# design.net
KiCad netlist of a schematic drawn in Altium Designer
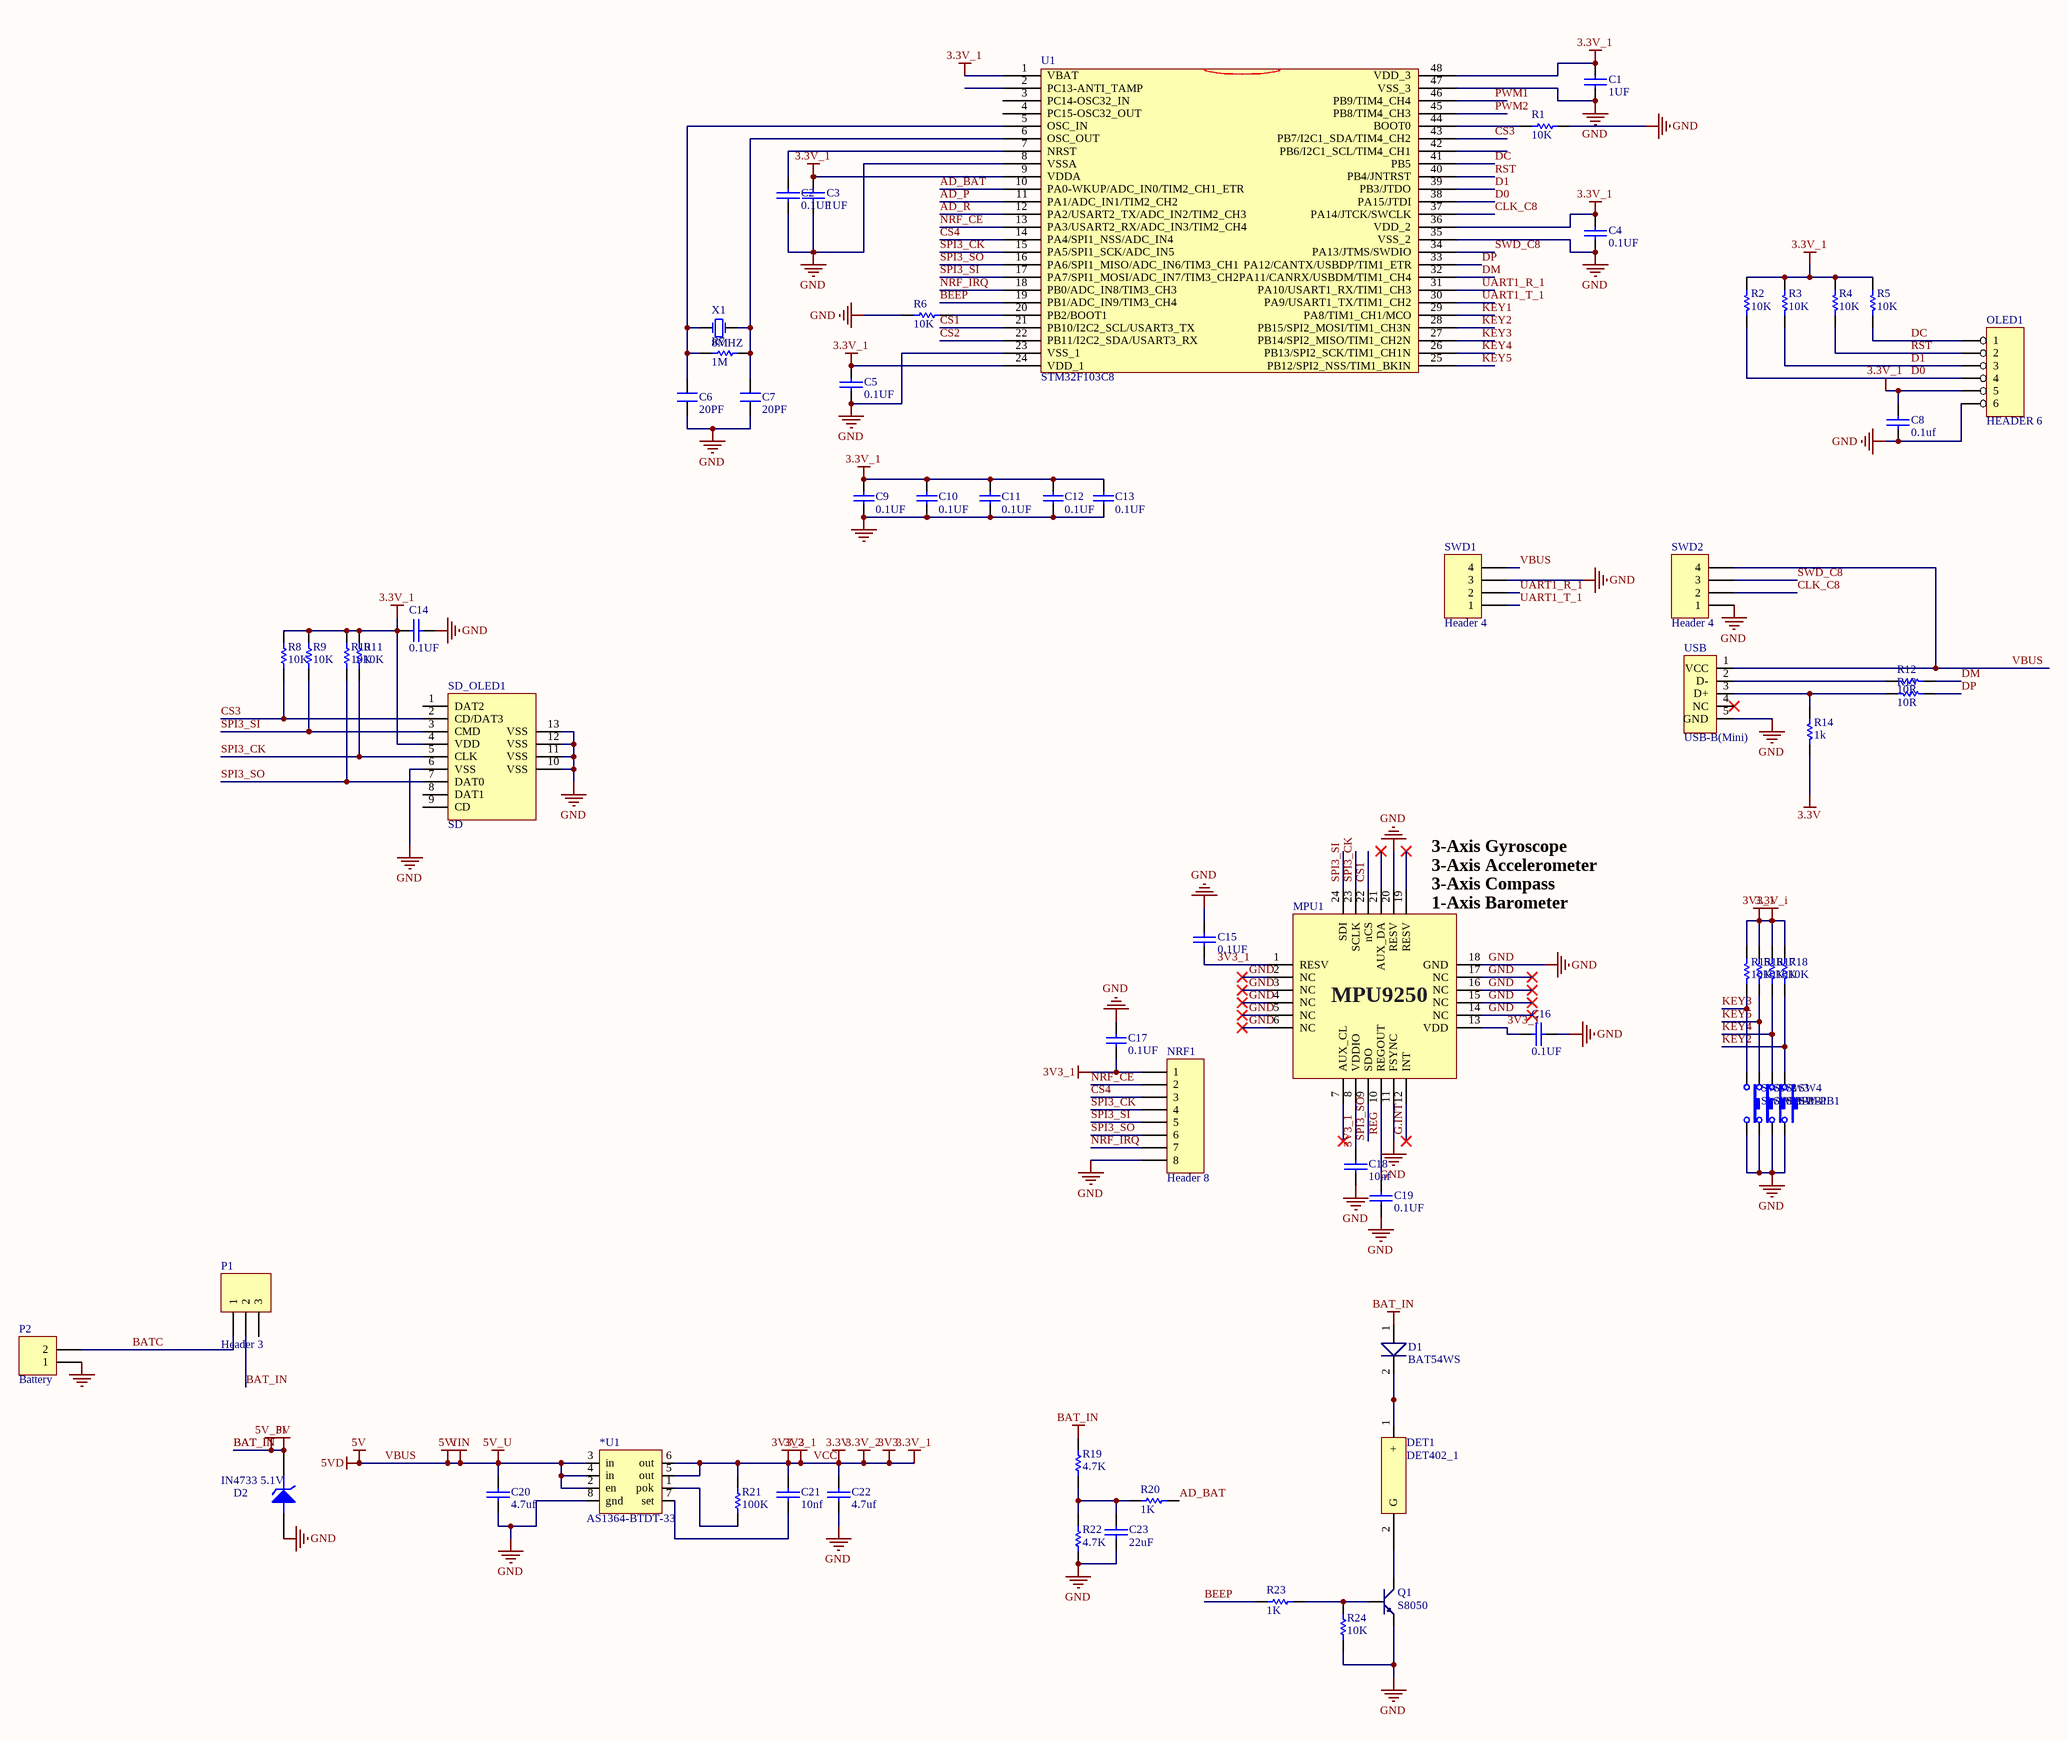
[diagram p0: 遥控器.SchDoc]

(export (version "E")
  (design (tool "Eeschema 10.0.6"))
  (components
    (comp (ref "*U1")
      (value "AS1364-BTDT-33")
      (footprint "TDFN-8")
      (libsource (lib "Schlib1_hand") (part "AS1364-3.3V"))
    )
    (comp (ref "C1")
      (value "1UF")
      (footprint "C 0402")
      (description "Capacitor")
      (libsource (lib "*") (part "CAP"))
    )
    (comp (ref "C2")
      (value "0.1UF")
      (footprint "C 0402")
      (description "Capacitor")
      (libsource (lib "*") (part "CAP"))
    )
    (comp (ref "C3")
      (value "1UF")
      (footprint "C 0402")
      (description "Capacitor")
      (libsource (lib "*") (part "CAP"))
    )
    (comp (ref "C4")
      (value "0.1UF")
      (footprint "C 0402")
      (description "Capacitor")
      (libsource (lib "*") (part "CAP"))
    )
    (comp (ref "C5")
      (value "0.1UF")
      (footprint "C 0402")
      (description "Capacitor")
      (libsource (lib "*") (part "CAP"))
    )
    (comp (ref "C6")
      (value "20PF")
      (footprint "C 0402")
      (description "0805")
      (libsource (lib "stm32f429i") (part "C2"))
    )
    (comp (ref "C7")
      (value "20PF")
      (footprint "C 0402")
      (description "0805")
      (libsource (lib "stm32f429i") (part "C2"))
    )
    (comp (ref "C8")
      (value "0.1uf")
      (footprint "C 0402")
      (description "Capacitor")
      (libsource (lib "*") (part "CAP"))
    )
    (comp (ref "C9")
      (value "0.1UF")
      (footprint "C 0402")
      (description "Capacitor")
      (fields (field (name "PUBLISHER") "Altium Limited"))
      (libsource (lib "Miscellaneous Devices") (part "CAP"))
    )
    (comp (ref "C10")
      (value "0.1UF")
      (footprint "C 0402")
      (description "Capacitor")
      (fields (field (name "PUBLISHER") "Altium Limited"))
      (libsource (lib "Miscellaneous Devices") (part "CAP"))
    )
    (comp (ref "C11")
      (value "0.1UF")
      (footprint "C 0402")
      (description "Capacitor")
      (fields (field (name "PUBLISHER") "Altium Limited"))
      (libsource (lib "Miscellaneous Devices") (part "CAP"))
    )
    (comp (ref "C12")
      (value "0.1UF")
      (footprint "C 0402")
      (description "Capacitor")
      (fields (field (name "PUBLISHER") "Altium Limited"))
      (libsource (lib "Miscellaneous Devices") (part "CAP"))
    )
    (comp (ref "C13")
      (value "0.1UF")
      (footprint "C 0402")
      (description "Capacitor")
      (fields (field (name "PUBLISHER") "Altium Limited"))
      (libsource (lib "Miscellaneous Devices") (part "CAP"))
    )
    (comp (ref "C14")
      (value "0.1UF")
      (footprint "C 0402")
      (description "Capacitor")
      (libsource (lib "*") (part "CAP"))
    )
    (comp (ref "C15")
      (value "0.1UF")
      (footprint "C 0402")
      (description "Capacitor")
      (libsource (lib "*") (part "CAP"))
    )
    (comp (ref "C16")
      (value "0.1UF")
      (footprint "C 0402")
      (description "Capacitor")
      (libsource (lib "*") (part "CAP"))
    )
    (comp (ref "C17")
      (value "0.1UF")
      (footprint "C 0402")
      (description "Capacitor")
      (fields (field (name "PUBLISHER") "Altium Limited"))
      (libsource (lib "Miscellaneous Devices") (part "CAP"))
    )
    (comp (ref "C18")
      (value "10nf")
      (footprint "C 0402")
      (description "Capacitor")
      (libsource (lib "*") (part "CAP"))
    )
    (comp (ref "C19")
      (value "0.1UF")
      (footprint "C 0402")
      (description "Capacitor")
      (libsource (lib "*") (part "CAP"))
    )
    (comp (ref "C20")
      (value "4.7uf")
      (footprint "C 0402")
      (description "Capacitor")
      (libsource (lib "*") (part "CAP"))
    )
    (comp (ref "C21")
      (value "10nf")
      (footprint "C 0402")
      (description "Capacitor")
      (libsource (lib "*") (part "CAP"))
    )
    (comp (ref "C22")
      (value "4.7uf")
      (footprint "C 0402")
      (description "Capacitor")
      (libsource (lib "*") (part "CAP"))
    )
    (comp (ref "C23")
      (value "22uF")
      (footprint "C 0402")
      (description "Capacitor")
      (libsource (lib "*") (part "CAP"))
    )
    (comp (ref "D1")
      (value "BAT54WS")
      (footprint "SOD-323")
      (description "单肖特基二极管")
      (libsource (lib "MiniFly ") (part "BAT54"))
    )
    (comp (ref "D2")
      (value "IN4733 5.1V")
      (footprint "1n4148-SOD123")
      (description "Zener Diode")
      (libsource (lib "*") (part "ZENER3"))
    )
    (comp (ref "DET1") (value "DET402_1") (footprint "DET402") (libsource (lib "EXPLORER") (part "DET402_1")))
    (comp (ref "MPU1")
      (value "MPU9250")
      (footprint "EXPLORER:MPU_QFN24_0.4")
      (description "Sensor")
      (libsource (lib "SCH_IC") (part "MPU9250"))
    )
    (comp (ref "NRF1")
      (value "Header 8")
      (footprint "NRF")
      (description "Header, 8-Pin")
      (fields (field (name "PUBLISHER") "Altium Limited"))
      (libsource (lib "Miscellaneous Connectors") (part "Header 8"))
    )
    (comp (ref "OLED1")
      (value "HEADER 6")
      (footprint "HDR1X6")
      (libsource (lib "Miscellaneous Devices") (part "HEADER 6"))
    )
    (comp (ref "P1")
      (value "Header 3")
      (footprint "HDR1X3")
      (description "Header, 3-Pin")
      (fields (field (name "PUBLISHER") "Altium Limited"))
      (libsource (lib "Miscellaneous Connectors") (part "Header 3"))
    )
    (comp (ref "P2")
      (value "Battery")
      (footprint "HDR1X2")
      (description "Header, 2-Pin")
      (fields (field (name "PUBLISHER") "Altium Limited"))
      (libsource (lib "MiniFly ") (part "Header 2"))
    )
    (comp (ref "Q1")
      (value "S8050")
      (footprint "SOT-23R")
      (description "8050/BCW846/BCW847")
      (libsource (lib "EXPLORER") (part "NPN"))
    )
    (comp (ref "R1")
      (value "10K")
      (footprint "R 0402")
      (description "Resistor")
      (fields (field (name "Comment") "1K") (field (name "PUBLISHER") "Altium Limited"))
      (libsource (lib "Miscellaneous Devices") (part "Res1"))
    )
    (comp (ref "R2")
      (value "10K")
      (footprint "R 0402")
      (description "0603")
      (libsource (lib "") (part "Res2_1"))
    )
    (comp (ref "R3")
      (value "10K")
      (footprint "R 0402")
      (description "0603")
      (libsource (lib "") (part "Res2_1"))
    )
    (comp (ref "R4")
      (value "10K")
      (footprint "R 0402")
      (description "0603")
      (libsource (lib "") (part "Res2_1"))
    )
    (comp (ref "R5")
      (value "10K")
      (footprint "R 0402")
      (description "0603")
      (libsource (lib "") (part "Res2_1"))
    )
    (comp (ref "R6")
      (value "10K")
      (footprint "R 0402")
      (description "Resistor")
      (fields (field (name "Comment") "1K") (field (name "PUBLISHER") "Altium Limited"))
      (libsource (lib "Miscellaneous Devices") (part "Res1"))
    )
    (comp (ref "R7")
      (value "1M")
      (footprint "R 0402")
      (description "0603")
      (libsource (lib "stm32f429i") (part "Res2"))
    )
    (comp (ref "R8")
      (value "10K")
      (footprint "R 0402")
      (description "0603")
      (libsource (lib "stm32f429i") (part "Res2"))
    )
    (comp (ref "R9")
      (value "10K")
      (footprint "R 0402")
      (description "0603")
      (libsource (lib "stm32f429i") (part "Res2"))
    )
    (comp (ref "R10")
      (value "10K")
      (footprint "R 0402")
      (description "0603")
      (libsource (lib "stm32f429i") (part "Res2"))
    )
    (comp (ref "R11")
      (value "10K")
      (footprint "R 0402")
      (description "0603")
      (libsource (lib "stm32f429i") (part "Res2"))
    )
    (comp (ref "R12")
      (value "10R")
      (footprint "R 0402")
      (description "0603")
      (libsource (lib "stm32f429i") (part "Res2"))
    )
    (comp (ref "R13")
      (value "10R")
      (footprint "R 0402")
      (description "0603")
      (libsource (lib "stm32f429i") (part "Res2"))
    )
    (comp (ref "R14")
      (value "1k")
      (footprint "R 0402")
      (description "0603")
      (libsource (lib "") (part "Res2_1"))
    )
    (comp (ref "R15")
      (value "10K")
      (footprint "R 0402")
      (description "Resistor")
      (fields (field (name "PUBLISHER") "Altium Limited"))
      (libsource (lib "Miscellaneous Devices") (part "Res1"))
    )
    (comp (ref "R16")
      (value "10K")
      (footprint "R 0402")
      (description "Resistor")
      (fields (field (name "PUBLISHER") "Altium Limited"))
      (libsource (lib "Miscellaneous Devices") (part "Res1"))
    )
    (comp (ref "R17")
      (value "10K")
      (footprint "R 0402")
      (description "Resistor")
      (fields (field (name "PUBLISHER") "Altium Limited"))
      (libsource (lib "Miscellaneous Devices") (part "Res1"))
    )
    (comp (ref "R18")
      (value "10K")
      (footprint "R 0402")
      (description "Resistor")
      (fields (field (name "PUBLISHER") "Altium Limited"))
      (libsource (lib "Miscellaneous Devices") (part "Res1"))
    )
    (comp (ref "R19")
      (value "4.7K")
      (footprint "R 0402")
      (description "0603")
      (libsource (lib "stm32f429i") (part "Res2"))
    )
    (comp (ref "R20")
      (value "1K")
      (footprint "R 0402")
      (description "0603")
      (libsource (lib "stm32f429i") (part "Res2"))
    )
    (comp (ref "R21")
      (value "100K")
      (footprint "R 0402")
      (description "Resistor")
      (fields (field (name "Comment") "1K") (field (name "PUBLISHER") "Altium Limited"))
      (libsource (lib "Miscellaneous Devices") (part "Res1"))
    )
    (comp (ref "R22")
      (value "4.7K")
      (footprint "R 0402")
      (description "0603")
      (libsource (lib "stm32f429i") (part "Res2"))
    )
    (comp (ref "R23")
      (value "1K")
      (footprint "R 0402")
      (description "0603")
      (libsource (lib "stm32f429i") (part "Res2"))
    )
    (comp (ref "R24")
      (value "10K")
      (footprint "R 0402")
      (description "0603")
      (libsource (lib "stm32f429i") (part "Res2"))
    )
    (comp (ref "SD_OLED1")
      (value "SD")
      (footprint "TF-MicroSD")
      (libsource (lib "stm32f429i") (part "TF-MicroSD"))
    )
    (comp (ref "SW1")
      (value "SW-PB1")
      (footprint "KEY_SAD")
      (description "按键")
      (libsource (lib "stm32f429i") (part "SW-PB"))
    )
    (comp (ref "SW2")
      (value "SW-PB1")
      (footprint "KEY_SAD")
      (description "按键")
      (libsource (lib "stm32f429i") (part "SW-PB"))
    )
    (comp (ref "SW3")
      (value "SW-PB1")
      (footprint "KEY_SAD")
      (description "按键")
      (libsource (lib "stm32f429i") (part "SW-PB"))
    )
    (comp (ref "SW4")
      (value "SW-PB1")
      (footprint "KEY_SAD")
      (description "按键")
      (libsource (lib "stm32f429i") (part "SW-PB"))
    )
    (comp (ref "SWD1")
      (value "Header 4")
      (footprint "JST_GH_V4")
      (description "Header, 4-Pin")
      (fields (field (name "PUBLISHER") "Altium Limited"))
      (libsource (lib "Explorer STM32F407封装库") (part "Header 4"))
    )
    (comp (ref "SWD2")
      (value "Header 4")
      (footprint "HDR1X4")
      (description "Header, 4-Pin")
      (fields (field (name "PUBLISHER") "Altium Limited"))
      (libsource (lib "Explorer STM32F407封装库") (part "Header 4"))
    )
    (comp (ref "U1")
      (value "STM32F103C8")
      (footprint "LQFP48S")
      (libsource (lib "STM32") (part "STM32F103C6"))
    )
    (comp (ref "USB")
      (value "USB-B(Mini)")
      (footprint "USB/SM0.8-6H5_M")
      (libsource (lib "EXPLORER") (part "USB5"))
    )
    (comp (ref "X1")
      (value "8MHZ")
      (footprint "PXCL")
      (description "Crystal Oscillator")
      (fields (field (name "PUBLISHER") "Altium Limited"))
      (libsource (lib "stm32f429i") (part "XTAL"))
    )
  )
  (nets
    (net (code "1") (name "/AD_BAT") (class "Default")
      (node (ref "R20") (pin "1") (pinfunction "1_1") (pintype "passive"))
      (node (ref "U1") (pin "10") (pinfunction "PA0-WKUP/ADC_IN0/TIM2_CH1_ETR_10") (pintype "passive"))
    )
    (net (code "2") (name "/AD_P") (class "Default")
      (node (ref "U1") (pin "11") (pinfunction "PA1/ADC_IN1/TIM2_CH2_11") (pintype "passive"))
    )
    (net (code "3") (name "/AD_R") (class "Default")
      (node (ref "U1") (pin "12") (pinfunction "PA2/USART2_TX/ADC_IN2/TIM2_CH3_12") (pintype "passive"))
    )
    (net (code "4") (name "/BATC") (class "Default")
      (node (ref "P1") (pin "1") (pinfunction "1_1") (pintype "passive"))
      (node (ref "P2") (pin "2") (pinfunction "2_2") (pintype "passive"))
    )
    (net (code "5") (name "/BEEP") (class "Default")
      (node (ref "R23") (pin "2") (pinfunction "2_2") (pintype "passive"))
      (node (ref "U1") (pin "19") (pinfunction "PB1/ADC_IN9/TIM3_CH4_19") (pintype "passive"))
    )
    (net (code "6") (name "/CLK_C8") (class "Default")
      (node (ref "SWD2") (pin "2") (pinfunction "2_2") (pintype "passive"))
      (node (ref "U1") (pin "37") (pinfunction "PA14/JTCK/SWCLK_37") (pintype "passive"))
    )
    (net (code "7") (name "/CS1") (class "Default")
      (node (ref "MPU1") (pin "22") (pinfunction "nCS_22") (pintype "passive"))
      (node (ref "U1") (pin "21") (pinfunction "PB10/I2C2_SCL/USART3_TX_21") (pintype "passive"))
    )
    (net (code "8") (name "/CS2") (class "Default")
      (node (ref "U1") (pin "22") (pinfunction "PB11/I2C2_SDA/USART3_RX_22") (pintype "passive"))
    )
    (net (code "9") (name "/CS3") (class "Default")
      (node (ref "R8") (pin "2") (pinfunction "2_2") (pintype "passive"))
      (node (ref "SD_OLED1") (pin "2") (pinfunction "CD/DAT3_2") (pintype "passive"))
      (node (ref "U1") (pin "43") (pinfunction "PB7/I2C1_SDA/TIM4_CH2_43") (pintype "passive"))
    )
    (net (code "10") (name "/CS4") (class "Default")
      (node (ref "NRF1") (pin "3") (pinfunction "3_3") (pintype "passive"))
      (node (ref "U1") (pin "14") (pinfunction "PA4/SPI1_NSS/ADC_IN4_14") (pintype "passive"))
    )
    (net (code "11") (name "/D0") (class "Default")
      (node (ref "OLED1") (pin "4") (pinfunction "4_4") (pintype "passive"))
      (node (ref "R2") (pin "1") (pinfunction "1_1") (pintype "passive"))
      (node (ref "U1") (pin "38") (pinfunction "PA15/JTDI_38") (pintype "passive"))
    )
    (net (code "12") (name "/D1") (class "Default")
      (node (ref "OLED1") (pin "3") (pinfunction "3_3") (pintype "passive"))
      (node (ref "R3") (pin "1") (pinfunction "1_1") (pintype "passive"))
      (node (ref "U1") (pin "39") (pinfunction "PB3/JTDO_39") (pintype "passive"))
    )
    (net (code "13") (name "/DC") (class "Default")
      (node (ref "OLED1") (pin "1") (pinfunction "1_1") (pintype "passive"))
      (node (ref "R5") (pin "1") (pinfunction "1_1") (pintype "passive"))
      (node (ref "U1") (pin "41") (pinfunction "PB5_41") (pintype "passive"))
    )
    (net (code "14") (name "/DM") (class "Default")
      (node (ref "R12") (pin "2") (pinfunction "2_2") (pintype "passive"))
      (node (ref "U1") (pin "32") (pinfunction "PA11/CANRX/USBDM/TIM1_CH4_32") (pintype "passive"))
    )
    (net (code "15") (name "/DP") (class "Default")
      (node (ref "R13") (pin "2") (pinfunction "2_2") (pintype "passive"))
      (node (ref "U1") (pin "33") (pinfunction "PA12/CANTX/USBDP/TIM1_ETR_33") (pintype "passive"))
    )
    (net (code "16") (name "/G.INT") (class "Default")
      (node (ref "MPU1") (pin "12") (pinfunction "INT_12") (pintype "passive+no_connect"))
    )
    (net (code "17") (name "/KEY1") (class "Default")
      (node (ref "U1") (pin "29") (pinfunction "PA8/TIM1_CH1/MCO_29") (pintype "passive"))
    )
    (net (code "18") (name "/KEY2") (class "Default")
      (node (ref "R18") (pin "1") (pinfunction "1_1") (pintype "passive"))
      (node (ref "SW4") (pin "2") (pinfunction "2_2") (pintype "passive"))
      (node (ref "U1") (pin "28") (pinfunction "PB15/SPI2_MOSI/TIM1_CH3N_28") (pintype "passive"))
    )
    (net (code "19") (name "/KEY3") (class "Default")
      (node (ref "R15") (pin "1") (pinfunction "1_1") (pintype "passive"))
      (node (ref "SW1") (pin "2") (pinfunction "2_2") (pintype "passive"))
      (node (ref "U1") (pin "27") (pinfunction "PB14/SPI2_MISO/TIM1_CH2N_27") (pintype "passive"))
    )
    (net (code "20") (name "/KEY4") (class "Default")
      (node (ref "R17") (pin "1") (pinfunction "1_1") (pintype "passive"))
      (node (ref "SW3") (pin "2") (pinfunction "2_2") (pintype "passive"))
      (node (ref "U1") (pin "26") (pinfunction "PB13/SPI2_SCK/TIM1_CH1N_26") (pintype "passive"))
    )
    (net (code "21") (name "/KEY5") (class "Default")
      (node (ref "R16") (pin "1") (pinfunction "1_1") (pintype "passive"))
      (node (ref "SW2") (pin "2") (pinfunction "2_2") (pintype "passive"))
      (node (ref "U1") (pin "25") (pinfunction "PB12/SPI2_NSS/TIM1_BKIN_25") (pintype "passive"))
    )
    (net (code "22") (name "/NRF_CE") (class "Default")
      (node (ref "NRF1") (pin "2") (pinfunction "2_2") (pintype "passive"))
      (node (ref "U1") (pin "13") (pinfunction "PA3/USART2_RX/ADC_IN3/TIM2_CH4_13") (pintype "passive"))
    )
    (net (code "23") (name "/NRF_IRQ") (class "Default")
      (node (ref "NRF1") (pin "7") (pinfunction "7_7") (pintype "passive"))
      (node (ref "U1") (pin "18") (pinfunction "PB0/ADC_IN8/TIM3_CH3_18") (pintype "passive"))
    )
    (net (code "24") (name "/PWM1") (class "Default")
      (node (ref "U1") (pin "46") (pinfunction "PB9/TIM4_CH4_46") (pintype "passive"))
    )
    (net (code "25") (name "/PWM2") (class "Default")
      (node (ref "U1") (pin "45") (pinfunction "PB8/TIM4_CH3_45") (pintype "passive"))
    )
    (net (code "26") (name "/REG") (class "Default")
      (node (ref "C19") (pin "2") (pinfunction "2_2") (pintype "passive"))
      (node (ref "MPU1") (pin "10") (pinfunction "REGOUT_10") (pintype "passive"))
    )
    (net (code "27") (name "/RST") (class "Default")
      (node (ref "OLED1") (pin "2") (pinfunction "2_2") (pintype "passive"))
      (node (ref "R4") (pin "1") (pinfunction "1_1") (pintype "passive"))
      (node (ref "U1") (pin "40") (pinfunction "PB4/JNTRST_40") (pintype "passive"))
    )
    (net (code "28") (name "/SPI3_CK") (class "Default")
      (node (ref "MPU1") (pin "23") (pinfunction "SCLK_23") (pintype "passive"))
      (node (ref "NRF1") (pin "4") (pinfunction "4_4") (pintype "passive"))
      (node (ref "R11") (pin "2") (pinfunction "2_2") (pintype "passive"))
      (node (ref "SD_OLED1") (pin "5") (pinfunction "CLK_5") (pintype "passive"))
      (node (ref "U1") (pin "15") (pinfunction "PA5/SPI1_SCK/ADC_IN5_15") (pintype "passive"))
    )
    (net (code "29") (name "/SPI3_SI") (class "Default")
      (node (ref "MPU1") (pin "24") (pinfunction "SDI_24") (pintype "passive"))
      (node (ref "NRF1") (pin "5") (pinfunction "5_5") (pintype "passive"))
      (node (ref "R9") (pin "2") (pinfunction "2_2") (pintype "passive"))
      (node (ref "SD_OLED1") (pin "3") (pinfunction "CMD_3") (pintype "passive"))
      (node (ref "U1") (pin "17") (pinfunction "PA7/SPI1_MOSI/ADC_IN7/TIM3_CH2_17") (pintype "passive"))
    )
    (net (code "30") (name "/SPI3_SO") (class "Default")
      (node (ref "MPU1") (pin "9") (pinfunction "SDO_9") (pintype "passive"))
      (node (ref "NRF1") (pin "6") (pinfunction "6_6") (pintype "passive"))
      (node (ref "R10") (pin "2") (pinfunction "2_2") (pintype "passive"))
      (node (ref "SD_OLED1") (pin "7") (pinfunction "DAT0_7") (pintype "passive"))
      (node (ref "U1") (pin "16") (pinfunction "PA6/SPI1_MISO/ADC_IN6/TIM3_CH1_16") (pintype "passive"))
    )
    (net (code "31") (name "/SWD_C8") (class "Default")
      (node (ref "SWD2") (pin "3") (pinfunction "3_3") (pintype "passive"))
      (node (ref "U1") (pin "34") (pinfunction "PA13/JTMS/SWDIO_34") (pintype "passive"))
    )
    (net (code "32") (name "/UART1_R_1") (class "Default")
      (node (ref "SWD1") (pin "2") (pinfunction "2_2") (pintype "passive"))
      (node (ref "U1") (pin "31") (pinfunction "PA10/USART1_RX/TIM1_CH3_31") (pintype "passive"))
    )
    (net (code "33") (name "/UART1_T_1") (class "Default")
      (node (ref "SWD1") (pin "1") (pinfunction "1_1") (pintype "passive"))
      (node (ref "U1") (pin "30") (pinfunction "PA9/USART1_TX/TIM1_CH2_30") (pintype "passive"))
    )
    (net (code "34") (name "3.3V") (class "Default")
      (node (ref "*U1") (pin "5") (pinfunction "out_5") (pintype "passive"))
      (node (ref "*U1") (pin "6") (pinfunction "out_6") (pintype "passive"))
      (node (ref "C1") (pin "2") (pinfunction "2_2") (pintype "passive"))
      (node (ref "C10") (pin "1") (pinfunction "1_1") (pintype "passive"))
      (node (ref "C11") (pin "1") (pinfunction "1_1") (pintype "passive"))
      (node (ref "C12") (pin "1") (pinfunction "1_1") (pintype "passive"))
      (node (ref "C13") (pin "1") (pinfunction "1_1") (pintype "passive"))
      (node (ref "C14") (pin "2") (pinfunction "2_2") (pintype "passive"))
      (node (ref "C15") (pin "1") (pinfunction "1_1") (pintype "passive"))
      (node (ref "C16") (pin "1") (pinfunction "1_1") (pintype "passive"))
      (node (ref "C17") (pin "1") (pinfunction "1_1") (pintype "passive"))
      (node (ref "C18") (pin "2") (pinfunction "2_2") (pintype "passive"))
      (node (ref "C21") (pin "1") (pinfunction "1_1") (pintype "passive"))
      (node (ref "C22") (pin "1") (pinfunction "1_1") (pintype "passive"))
      (node (ref "C3") (pin "2") (pinfunction "2_2") (pintype "passive"))
      (node (ref "C4") (pin "2") (pinfunction "2_2") (pintype "passive"))
      (node (ref "C5") (pin "2") (pinfunction "2_2") (pintype "passive"))
      (node (ref "C8") (pin "2") (pinfunction "2_2") (pintype "passive"))
      (node (ref "C9") (pin "1") (pinfunction "1_1") (pintype "passive"))
      (node (ref "MPU1") (pin "1") (pinfunction "RESV_1") (pintype "passive"))
      (node (ref "MPU1") (pin "13") (pinfunction "VDD_13") (pintype "passive"))
      (node (ref "MPU1") (pin "8") (pinfunction "VDDIO_8") (pintype "passive"))
      (node (ref "NRF1") (pin "1") (pinfunction "1_1") (pintype "passive"))
      (node (ref "OLED1") (pin "5") (pinfunction "5_5") (pintype "passive"))
      (node (ref "R10") (pin "1") (pinfunction "1_1") (pintype "passive"))
      (node (ref "R11") (pin "1") (pinfunction "1_1") (pintype "passive"))
      (node (ref "R14") (pin "1") (pinfunction "1_1") (pintype "passive"))
      (node (ref "R15") (pin "2") (pinfunction "2_2") (pintype "passive"))
      (node (ref "R16") (pin "2") (pinfunction "2_2") (pintype "passive"))
      (node (ref "R17") (pin "2") (pinfunction "2_2") (pintype "passive"))
      (node (ref "R18") (pin "2") (pinfunction "2_2") (pintype "passive"))
      (node (ref "R2") (pin "2") (pinfunction "2_2") (pintype "passive"))
      (node (ref "R21") (pin "1") (pinfunction "1_1") (pintype "passive"))
      (node (ref "R3") (pin "2") (pinfunction "2_2") (pintype "passive"))
      (node (ref "R4") (pin "2") (pinfunction "2_2") (pintype "passive"))
      (node (ref "R5") (pin "2") (pinfunction "2_2") (pintype "passive"))
      (node (ref "R8") (pin "1") (pinfunction "1_1") (pintype "passive"))
      (node (ref "R9") (pin "1") (pinfunction "1_1") (pintype "passive"))
      (node (ref "SD_OLED1") (pin "4") (pinfunction "VDD_4") (pintype "passive"))
      (node (ref "U1") (pin "1") (pinfunction "VBAT_1") (pintype "passive"))
      (node (ref "U1") (pin "24") (pinfunction "VDD_1_24") (pintype "passive"))
      (node (ref "U1") (pin "36") (pinfunction "VDD_2_36") (pintype "passive"))
      (node (ref "U1") (pin "48") (pinfunction "VDD_3_48") (pintype "passive"))
      (node (ref "U1") (pin "9") (pinfunction "VDDA_9") (pintype "passive"))
    )
    (net (code "35") (name "5V") (class "Default")
      (node (ref "*U1") (pin "2") (pinfunction "en_2") (pintype "passive"))
      (node (ref "*U1") (pin "3") (pinfunction "in_3") (pintype "passive"))
      (node (ref "*U1") (pin "4") (pinfunction "in_4") (pintype "passive"))
      (node (ref "C20") (pin "1") (pinfunction "1_1") (pintype "passive"))
      (node (ref "D1") (pin "1") (pinfunction "1_1") (pintype "passive"))
      (node (ref "D2") (pin "2") (pinfunction "K_2") (pintype "passive"))
      (node (ref "P1") (pin "2") (pinfunction "2_2") (pintype "passive"))
      (node (ref "R19") (pin "2") (pinfunction "2_2") (pintype "passive"))
      (node (ref "SWD1") (pin "4") (pinfunction "4_4") (pintype "passive"))
      (node (ref "SWD2") (pin "4") (pinfunction "4_4") (pintype "passive"))
      (node (ref "USB") (pin "1") (pinfunction "VCC_1") (pintype "passive"))
    )
    (net (code "36") (name "GND") (class "Default")
      (node (ref "*U1") (pin "8") (pinfunction "gnd_8") (pintype "passive"))
      (node (ref "C1") (pin "1") (pinfunction "1_1") (pintype "passive"))
      (node (ref "C10") (pin "2") (pinfunction "2_2") (pintype "passive"))
      (node (ref "C11") (pin "2") (pinfunction "2_2") (pintype "passive"))
      (node (ref "C12") (pin "2") (pinfunction "2_2") (pintype "passive"))
      (node (ref "C13") (pin "2") (pinfunction "2_2") (pintype "passive"))
      (node (ref "C14") (pin "1") (pinfunction "1_1") (pintype "passive"))
      (node (ref "C15") (pin "2") (pinfunction "2_2") (pintype "passive"))
      (node (ref "C16") (pin "2") (pinfunction "2_2") (pintype "passive"))
      (node (ref "C17") (pin "2") (pinfunction "2_2") (pintype "passive"))
      (node (ref "C18") (pin "1") (pinfunction "1_1") (pintype "passive"))
      (node (ref "C19") (pin "1") (pinfunction "1_1") (pintype "passive"))
      (node (ref "C2") (pin "1") (pinfunction "1_1") (pintype "passive"))
      (node (ref "C20") (pin "2") (pinfunction "2_2") (pintype "passive"))
      (node (ref "C22") (pin "2") (pinfunction "2_2") (pintype "passive"))
      (node (ref "C23") (pin "2") (pinfunction "2_2") (pintype "passive"))
      (node (ref "C3") (pin "1") (pinfunction "1_1") (pintype "passive"))
      (node (ref "C4") (pin "1") (pinfunction "1_1") (pintype "passive"))
      (node (ref "C5") (pin "1") (pinfunction "1_1") (pintype "passive"))
      (node (ref "C6") (pin "1") (pintype "passive"))
      (node (ref "C7") (pin "1") (pintype "passive"))
      (node (ref "C8") (pin "1") (pinfunction "1_1") (pintype "passive"))
      (node (ref "C9") (pin "2") (pinfunction "2_2") (pintype "passive"))
      (node (ref "D2") (pin "1") (pinfunction "A_1") (pintype "passive"))
      (node (ref "MPU1") (pin "11") (pinfunction "FSYNC_11") (pintype "passive"))
      (node (ref "MPU1") (pin "14") (pinfunction "NC_14") (pintype "passive"))
      (node (ref "MPU1") (pin "15") (pinfunction "NC_15") (pintype "passive"))
      (node (ref "MPU1") (pin "16") (pinfunction "NC_16") (pintype "passive"))
      (node (ref "MPU1") (pin "17") (pinfunction "NC_17") (pintype "passive"))
      (node (ref "MPU1") (pin "18") (pinfunction "GND_18") (pintype "passive"))
      (node (ref "MPU1") (pin "2") (pinfunction "NC_2") (pintype "passive"))
      (node (ref "MPU1") (pin "20") (pinfunction "RESV_20") (pintype "passive"))
      (node (ref "MPU1") (pin "3") (pinfunction "NC_3") (pintype "passive"))
      (node (ref "MPU1") (pin "4") (pinfunction "NC_4") (pintype "passive"))
      (node (ref "MPU1") (pin "5") (pinfunction "NC_5") (pintype "passive"))
      (node (ref "MPU1") (pin "6") (pinfunction "NC_6") (pintype "passive"))
      (node (ref "NRF1") (pin "8") (pinfunction "8_8") (pintype "passive"))
      (node (ref "OLED1") (pin "6") (pinfunction "6_6") (pintype "passive"))
      (node (ref "P2") (pin "1") (pinfunction "1_1") (pintype "passive"))
      (node (ref "Q1") (pin "1") (pinfunction "E_1") (pintype "passive"))
      (node (ref "R1") (pin "2") (pinfunction "2_2") (pintype "passive"))
      (node (ref "R22") (pin "1") (pinfunction "1_1") (pintype "passive"))
      (node (ref "R24") (pin "1") (pinfunction "1_1") (pintype "passive"))
      (node (ref "R6") (pin "1") (pinfunction "1_1") (pintype "passive"))
      (node (ref "SD_OLED1") (pin "10") (pinfunction "VSS_10") (pintype "passive"))
      (node (ref "SD_OLED1") (pin "11") (pinfunction "VSS_11") (pintype "passive"))
      (node (ref "SD_OLED1") (pin "12") (pinfunction "VSS_12") (pintype "passive"))
      (node (ref "SD_OLED1") (pin "13") (pinfunction "VSS_13") (pintype "passive"))
      (node (ref "SD_OLED1") (pin "6") (pinfunction "VSS_6") (pintype "passive"))
      (node (ref "SW1") (pin "1") (pinfunction "1_1") (pintype "passive"))
      (node (ref "SW2") (pin "1") (pinfunction "1_1") (pintype "passive"))
      (node (ref "SW3") (pin "1") (pinfunction "1_1") (pintype "passive"))
      (node (ref "SW4") (pin "1") (pinfunction "1_1") (pintype "passive"))
      (node (ref "SWD1") (pin "3") (pinfunction "3_3") (pintype "passive"))
      (node (ref "SWD2") (pin "1") (pinfunction "1_1") (pintype "passive"))
      (node (ref "U1") (pin "23") (pinfunction "VSS_1_23") (pintype "passive"))
      (node (ref "U1") (pin "35") (pinfunction "VSS_2_35") (pintype "passive"))
      (node (ref "U1") (pin "47") (pinfunction "VSS_3_47") (pintype "passive"))
      (node (ref "U1") (pin "8") (pinfunction "VSSA_8") (pintype "passive"))
      (node (ref "USB") (pin "5") (pinfunction "GND_5") (pintype "passive"))
    )
    (net (code "37") (name "Net-(*U1-pok)") (class "Default")
      (node (ref "*U1") (pin "1") (pinfunction "pok_1") (pintype "passive"))
      (node (ref "R21") (pin "2") (pinfunction "2_2") (pintype "passive"))
    )
    (net (code "38") (name "Net-(*U1-set)") (class "Default")
      (node (ref "*U1") (pin "7") (pinfunction "set_7") (pintype "passive"))
      (node (ref "C21") (pin "2") (pinfunction "2_2") (pintype "passive"))
    )
    (net (code "39") (name "Net-(C23-Pad1)") (class "Default")
      (node (ref "C23") (pin "1") (pinfunction "1_1") (pintype "passive"))
      (node (ref "R19") (pin "1") (pinfunction "1_1") (pintype "passive"))
      (node (ref "R20") (pin "2") (pinfunction "2_2") (pintype "passive"))
      (node (ref "R22") (pin "2") (pinfunction "2_2") (pintype "passive"))
    )
    (net (code "40") (name "Net-(DET1-+)") (class "Default")
      (node (ref "D1") (pin "2") (pinfunction "2_2") (pintype "passive"))
      (node (ref "DET1") (pin "1") (pinfunction "+_1") (pintype "passive"))
    )
    (net (code "41") (name "Net-(DET1-G)") (class "Default")
      (node (ref "DET1") (pin "2") (pinfunction "G_2") (pintype "passive"))
      (node (ref "Q1") (pin "3") (pinfunction "C_3") (pintype "passive"))
    )
    (net (code "42") (name "Net-(Q1-B)") (class "Default")
      (node (ref "Q1") (pin "2") (pinfunction "B_2") (pintype "passive"))
      (node (ref "R23") (pin "1") (pinfunction "1_1") (pintype "passive"))
      (node (ref "R24") (pin "2") (pinfunction "2_2") (pintype "passive"))
    )
    (net (code "43") (name "Net-(U1-BOOT0)") (class "Default")
      (node (ref "R1") (pin "1") (pinfunction "1_1") (pintype "passive"))
      (node (ref "U1") (pin "44") (pinfunction "BOOT0_44") (pintype "passive"))
    )
    (net (code "44") (name "Net-(U1-NRST)") (class "Default")
      (node (ref "C2") (pin "2") (pinfunction "2_2") (pintype "passive"))
      (node (ref "U1") (pin "7") (pinfunction "NRST_7") (pintype "passive"))
    )
    (net (code "45") (name "Net-(U1-OSC_IN)") (class "Default")
      (node (ref "C6") (pin "2") (pintype "passive"))
      (node (ref "R7") (pin "1") (pinfunction "1_1") (pintype "passive"))
      (node (ref "U1") (pin "5") (pinfunction "OSC_IN_5") (pintype "passive"))
      (node (ref "X1") (pin "1") (pinfunction "OSC1_1") (pintype "passive"))
    )
    (net (code "46") (name "Net-(U1-OSC_OUT)") (class "Default")
      (node (ref "C7") (pin "2") (pintype "passive"))
      (node (ref "R7") (pin "2") (pinfunction "2_2") (pintype "passive"))
      (node (ref "U1") (pin "6") (pinfunction "OSC_OUT_6") (pintype "passive"))
      (node (ref "X1") (pin "2") (pinfunction "OSC2_2") (pintype "passive"))
    )
    (net (code "47") (name "Net-(U1-PB2{slash}BOOT1)") (class "Default")
      (node (ref "R6") (pin "2") (pinfunction "2_2") (pintype "passive"))
      (node (ref "U1") (pin "20") (pinfunction "PB2/BOOT1_20") (pintype "passive"))
    )
    (net (code "48") (name "Net-(USB-D+)") (class "Default")
      (node (ref "R13") (pin "1") (pinfunction "1_1") (pintype "passive"))
      (node (ref "R14") (pin "2") (pinfunction "2_2") (pintype "passive"))
      (node (ref "USB") (pin "3") (pinfunction "D+_3") (pintype "passive"))
    )
    (net (code "49") (name "Net-(USB-D-)") (class "Default")
      (node (ref "R12") (pin "1") (pinfunction "1_1") (pintype "passive"))
      (node (ref "USB") (pin "2") (pinfunction "D-_2") (pintype "passive"))
    )
    (net (code "50") (name "unconnected-(MPU1-AUX_CL-Pad7)") (class "Default")
      (node (ref "MPU1") (pin "7") (pinfunction "AUX_CL_7") (pintype "passive+no_connect"))
    )
    (net (code "51") (name "unconnected-(MPU1-AUX_DA-Pad21)") (class "Default")
      (node (ref "MPU1") (pin "21") (pinfunction "AUX_DA_21") (pintype "passive+no_connect"))
    )
    (net (code "52") (name "unconnected-(MPU1-RESV-Pad19)") (class "Default")
      (node (ref "MPU1") (pin "19") (pinfunction "RESV_19") (pintype "passive+no_connect"))
    )
    (net (code "53") (name "unconnected-(P1-Pad3)") (class "Default")
      (node (ref "P1") (pin "3") (pinfunction "3_3") (pintype "passive"))
    )
    (net (code "54") (name "unconnected-(SD_OLED1-CD-Pad9)") (class "Default")
      (node (ref "SD_OLED1") (pin "9") (pinfunction "CD_9") (pintype "passive"))
    )
    (net (code "55") (name "unconnected-(SD_OLED1-DAT1-Pad8)") (class "Default")
      (node (ref "SD_OLED1") (pin "8") (pinfunction "DAT1_8") (pintype "passive"))
    )
    (net (code "56") (name "unconnected-(SD_OLED1-DAT2-Pad1)") (class "Default")
      (node (ref "SD_OLED1") (pin "1") (pinfunction "DAT2_1") (pintype "passive"))
    )
    (net (code "57") (name "unconnected-(U1-PB6{slash}I2C1_SCL{slash}TIM4_CH1-Pad42)") (class "Default")
      (node (ref "U1") (pin "42") (pinfunction "PB6/I2C1_SCL/TIM4_CH1_42") (pintype "passive"))
    )
    (net (code "58") (name "unconnected-(U1-PC13-ANTI_TAMP-Pad2)") (class "Default")
      (node (ref "U1") (pin "2") (pinfunction "PC13-ANTI_TAMP_2") (pintype "passive"))
    )
    (net (code "59") (name "unconnected-(U1-PC14-OSC32_IN-Pad3)") (class "Default")
      (node (ref "U1") (pin "3") (pinfunction "PC14-OSC32_IN_3") (pintype "passive"))
    )
    (net (code "60") (name "unconnected-(U1-PC15-OSC32_OUT-Pad4)") (class "Default")
      (node (ref "U1") (pin "4") (pinfunction "PC15-OSC32_OUT_4") (pintype "passive"))
    )
    (net (code "61") (name "unconnected-(USB-NC-Pad4)") (class "Default")
      (node (ref "USB") (pin "4") (pinfunction "NC_4") (pintype "passive+no_connect"))
    )
  )
)
